# Sheet1.net
KiCad netlist of a schematic drawn in Altium Designer
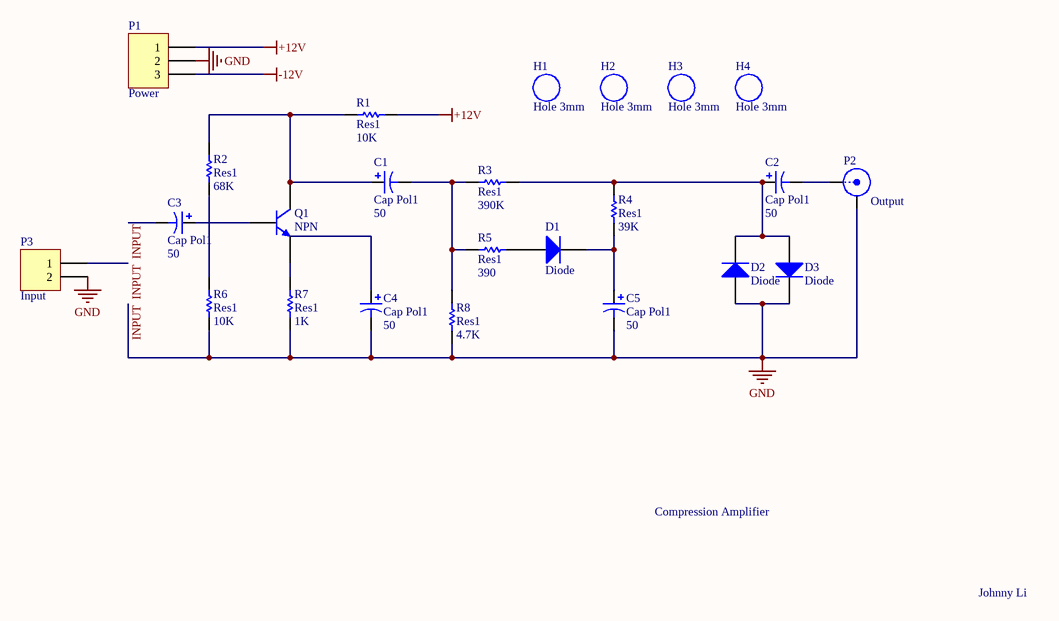
[diagram p0: Sheet1.SchDoc]

(export (version "E")
  (design (tool "Eeschema 10.0.6"))
  (components
    (comp (ref "C1")
      (value "Cap Pol1")
      (footprint "RB7.6-15")
      (description "Polarized Capacitor (Radial)")
      (fields (field (name "ALTIUM_VALUE") "50") (field (name "PUBLISHER") "Altium Limited"))
      (libsource (lib "") (part "Cap Pol1_1"))
    )
    (comp (ref "C2")
      (value "Cap Pol1")
      (footprint "RB7.6-15")
      (description "Polarized Capacitor (Radial)")
      (fields (field (name "ALTIUM_VALUE") "50") (field (name "PUBLISHER") "Altium Limited"))
      (libsource (lib "") (part "Cap Pol1_1"))
    )
    (comp (ref "C3")
      (value "Cap Pol1")
      (footprint "RB7.6-15")
      (description "Polarized Capacitor (Radial)")
      (fields (field (name "ALTIUM_VALUE") "50") (field (name "PUBLISHER") "Altium Limited"))
      (libsource (lib "Miscellaneous Devices") (part "Cap Pol1"))
    )
    (comp (ref "C4")
      (value "Cap Pol1")
      (footprint "RB7.6-15")
      (description "Polarized Capacitor (Radial)")
      (fields (field (name "ALTIUM_VALUE") "50") (field (name "PUBLISHER") "Altium Limited"))
      (libsource (lib "") (part "Cap Pol1_1"))
    )
    (comp (ref "C5")
      (value "Cap Pol1")
      (footprint "RB7.6-15")
      (description "Polarized Capacitor (Radial)")
      (fields (field (name "ALTIUM_VALUE") "50") (field (name "PUBLISHER") "Altium Limited"))
      (libsource (lib "") (part "Cap Pol1_1"))
    )
    (comp (ref "D1")
      (value "Diode")
      (footprint "SMC")
      (description "Default Diode")
      (fields (field (name "PUBLISHER") "Altium Limited"))
      (libsource (lib "Miscellaneous Devices") (part "Diode"))
    )
    (comp (ref "D2")
      (value "Diode")
      (footprint "SMC")
      (description "Default Diode")
      (fields (field (name "PUBLISHER") "Altium Limited"))
      (libsource (lib "Miscellaneous Devices") (part "Diode"))
    )
    (comp (ref "D3")
      (value "Diode")
      (footprint "SMC")
      (description "Default Diode")
      (fields (field (name "PUBLISHER") "Altium Limited"))
      (libsource (lib "Miscellaneous Devices") (part "Diode"))
    )
    (comp (ref "H1")
      (value "Hole 3mm")
      (footprint "Hole 3mm")
      (libsource (lib "ECE LIB new") (part "Hole 3mm"))
    )
    (comp (ref "H2")
      (value "Hole 3mm")
      (footprint "Hole 3mm")
      (libsource (lib "ECE LIB new") (part "Hole 3mm"))
    )
    (comp (ref "H3")
      (value "Hole 3mm")
      (footprint "Hole 3mm")
      (libsource (lib "ECE LIB new") (part "Hole 3mm"))
    )
    (comp (ref "H4")
      (value "Hole 3mm")
      (footprint "Hole 3mm")
      (libsource (lib "ECE LIB new") (part "Hole 3mm"))
    )
    (comp (ref "P1")
      (value "Power")
      (footprint "HDR1X3")
      (description "Header, 3-Pin")
      (fields (field (name "PUBLISHER") "Altium Limited"))
      (libsource (lib "Miscellaneous Connectors") (part "Header 3"))
    )
    (comp (ref "P2")
      (value "Output")
      (footprint "BNC_RA CON")
      (description "BNC Elbow Connector")
      (fields (field (name "PUBLISHER") "Altium Limited"))
      (libsource (lib "Miscellaneous Connectors") (part "BNC"))
    )
    (comp (ref "P3")
      (value "Input")
      (footprint "HDR1X2")
      (description "Header, 2-Pin")
      (fields (field (name "PUBLISHER") "Altium Limited"))
      (libsource (lib "Miscellaneous Connectors") (part "Header 2"))
    )
    (comp (ref "Q1")
      (value "NPN")
      (footprint "TO-226-AA")
      (description "NPN Bipolar Transistor")
      (fields (field (name "PUBLISHER") "Altium Limited"))
      (libsource (lib "Miscellaneous Devices") (part "NPN"))
    )
    (comp (ref "R1")
      (value "Res1")
      (footprint "AXIAL-0.3")
      (description "Resistor")
      (fields (field (name "ALTIUM_VALUE") "10K") (field (name "PUBLISHER") "Altium Limited"))
      (libsource (lib "Miscellaneous Devices") (part "Res1"))
    )
    (comp (ref "R2")
      (value "Res1")
      (footprint "AXIAL-0.3")
      (description "Resistor")
      (fields (field (name "ALTIUM_VALUE") "68K") (field (name "PUBLISHER") "Altium Limited"))
      (libsource (lib "Miscellaneous Devices") (part "Res1"))
    )
    (comp (ref "R3")
      (value "Res1")
      (footprint "AXIAL-0.3")
      (description "Resistor")
      (fields (field (name "ALTIUM_VALUE") "390K") (field (name "PUBLISHER") "Altium Limited"))
      (libsource (lib "Miscellaneous Devices") (part "Res1"))
    )
    (comp (ref "R4")
      (value "Res1")
      (footprint "AXIAL-0.3")
      (description "Resistor")
      (fields (field (name "ALTIUM_VALUE") "39K") (field (name "PUBLISHER") "Altium Limited"))
      (libsource (lib "Miscellaneous Devices") (part "Res1"))
    )
    (comp (ref "R5")
      (value "Res1")
      (footprint "AXIAL-0.3")
      (description "Resistor")
      (fields (field (name "ALTIUM_VALUE") "390") (field (name "PUBLISHER") "Altium Limited"))
      (libsource (lib "Miscellaneous Devices") (part "Res1"))
    )
    (comp (ref "R6")
      (value "Res1")
      (footprint "AXIAL-0.3")
      (description "Resistor")
      (fields (field (name "ALTIUM_VALUE") "10K") (field (name "PUBLISHER") "Altium Limited"))
      (libsource (lib "Miscellaneous Devices") (part "Res1"))
    )
    (comp (ref "R7")
      (value "Res1")
      (footprint "AXIAL-0.3")
      (description "Resistor")
      (fields (field (name "ALTIUM_VALUE") "1K") (field (name "PUBLISHER") "Altium Limited"))
      (libsource (lib "Miscellaneous Devices") (part "Res1"))
    )
    (comp (ref "R8")
      (value "Res1")
      (footprint "AXIAL-0.3")
      (description "Resistor")
      (fields (field (name "ALTIUM_VALUE") "4.7K") (field (name "PUBLISHER") "Altium Limited"))
      (libsource (lib "Miscellaneous Devices") (part "Res1"))
    )
  )
  (nets
    (net (code "1") (name "+12V") (class "Default")
      (node (ref "P1") (pin "1") (pinfunction "1_1") (pintype "passive"))
      (node (ref "R1") (pin "2") (pinfunction "2_2") (pintype "passive"))
    )
    (net (code "2") (name "-12V") (class "Default")
      (node (ref "P1") (pin "3") (pinfunction "3_3") (pintype "passive"))
    )
    (net (code "3") (name "GND") (class "Default")
      (node (ref "C3") (pin "2") (pinfunction "2_2") (pintype "passive"))
      (node (ref "C4") (pin "2") (pinfunction "2_2") (pintype "passive"))
      (node (ref "C5") (pin "2") (pinfunction "2_2") (pintype "passive"))
      (node (ref "D2") (pin "1") (pinfunction "A_1") (pintype "passive"))
      (node (ref "D3") (pin "2") (pinfunction "K_2") (pintype "passive"))
      (node (ref "P1") (pin "2") (pinfunction "2_2") (pintype "passive"))
      (node (ref "P2") (pin "2") (pinfunction "Y_2") (pintype "passive"))
      (node (ref "P3") (pin "1") (pinfunction "1_1") (pintype "passive"))
      (node (ref "P3") (pin "2") (pinfunction "2_2") (pintype "passive"))
      (node (ref "R6") (pin "1") (pinfunction "1_1") (pintype "passive"))
      (node (ref "R7") (pin "1") (pinfunction "1_1") (pintype "passive"))
      (node (ref "R8") (pin "1") (pinfunction "1_1") (pintype "passive"))
    )
    (net (code "4") (name "Net-(C1-Pad2)") (class "Default")
      (node (ref "C1") (pin "2") (pinfunction "2_2") (pintype "passive"))
      (node (ref "R3") (pin "2") (pinfunction "2_2") (pintype "passive"))
      (node (ref "R5") (pin "2") (pinfunction "2_2") (pintype "passive"))
      (node (ref "R8") (pin "2") (pinfunction "2_2") (pintype "passive"))
    )
    (net (code "5") (name "Net-(D1-A)") (class "Default")
      (node (ref "D1") (pin "1") (pinfunction "A_1") (pintype "passive"))
      (node (ref "R5") (pin "1") (pinfunction "1_1") (pintype "passive"))
    )
    (net (code "6") (name "Net-(D1-K)") (class "Default")
      (node (ref "C5") (pin "1") (pinfunction "1_1") (pintype "passive"))
      (node (ref "D1") (pin "2") (pinfunction "K_2") (pintype "passive"))
      (node (ref "R4") (pin "2") (pinfunction "2_2") (pintype "passive"))
    )
    (net (code "7") (name "Net-(D2-K)") (class "Default")
      (node (ref "C2") (pin "1") (pinfunction "1_1") (pintype "passive"))
      (node (ref "D2") (pin "2") (pinfunction "K_2") (pintype "passive"))
      (node (ref "D3") (pin "1") (pinfunction "A_1") (pintype "passive"))
      (node (ref "R3") (pin "1") (pinfunction "1_1") (pintype "passive"))
      (node (ref "R4") (pin "1") (pinfunction "1_1") (pintype "passive"))
    )
    (net (code "8") (name "Net-(P2-X)") (class "Default")
      (node (ref "C2") (pin "2") (pinfunction "2_2") (pintype "passive"))
      (node (ref "P2") (pin "1") (pinfunction "X_1") (pintype "passive"))
    )
    (net (code "9") (name "Net-(Q1-B)") (class "Default")
      (node (ref "C3") (pin "1") (pinfunction "1_1") (pintype "passive"))
      (node (ref "Q1") (pin "2") (pinfunction "B_2") (pintype "passive"))
    )
    (net (code "10") (name "Net-(Q1-C)") (class "Default")
      (node (ref "C1") (pin "1") (pinfunction "1_1") (pintype "passive"))
      (node (ref "Q1") (pin "1") (pinfunction "C_1") (pintype "passive"))
      (node (ref "R1") (pin "1") (pinfunction "1_1") (pintype "passive"))
      (node (ref "R2") (pin "2") (pinfunction "2_2") (pintype "passive"))
    )
    (net (code "11") (name "Net-(Q1-E)") (class "Default")
      (node (ref "Q1") (pin "3") (pinfunction "E_3") (pintype "passive"))
      (node (ref "R7") (pin "2") (pinfunction "2_2") (pintype "passive"))
    )
    (net (code "12") (name "Net-(R2-Pad1)") (class "Default")
      (node (ref "R2") (pin "1") (pinfunction "1_1") (pintype "passive"))
      (node (ref "R6") (pin "2") (pinfunction "2_2") (pintype "passive"))
    )
    (net (code "13") (name "unconnected-(C4-Pad1)") (class "Default")
      (node (ref "C4") (pin "1") (pinfunction "1_1") (pintype "passive"))
    )
  )
)
